# Flash_STM32.net
KiCad netlist of a schematic drawn in Altium Designer
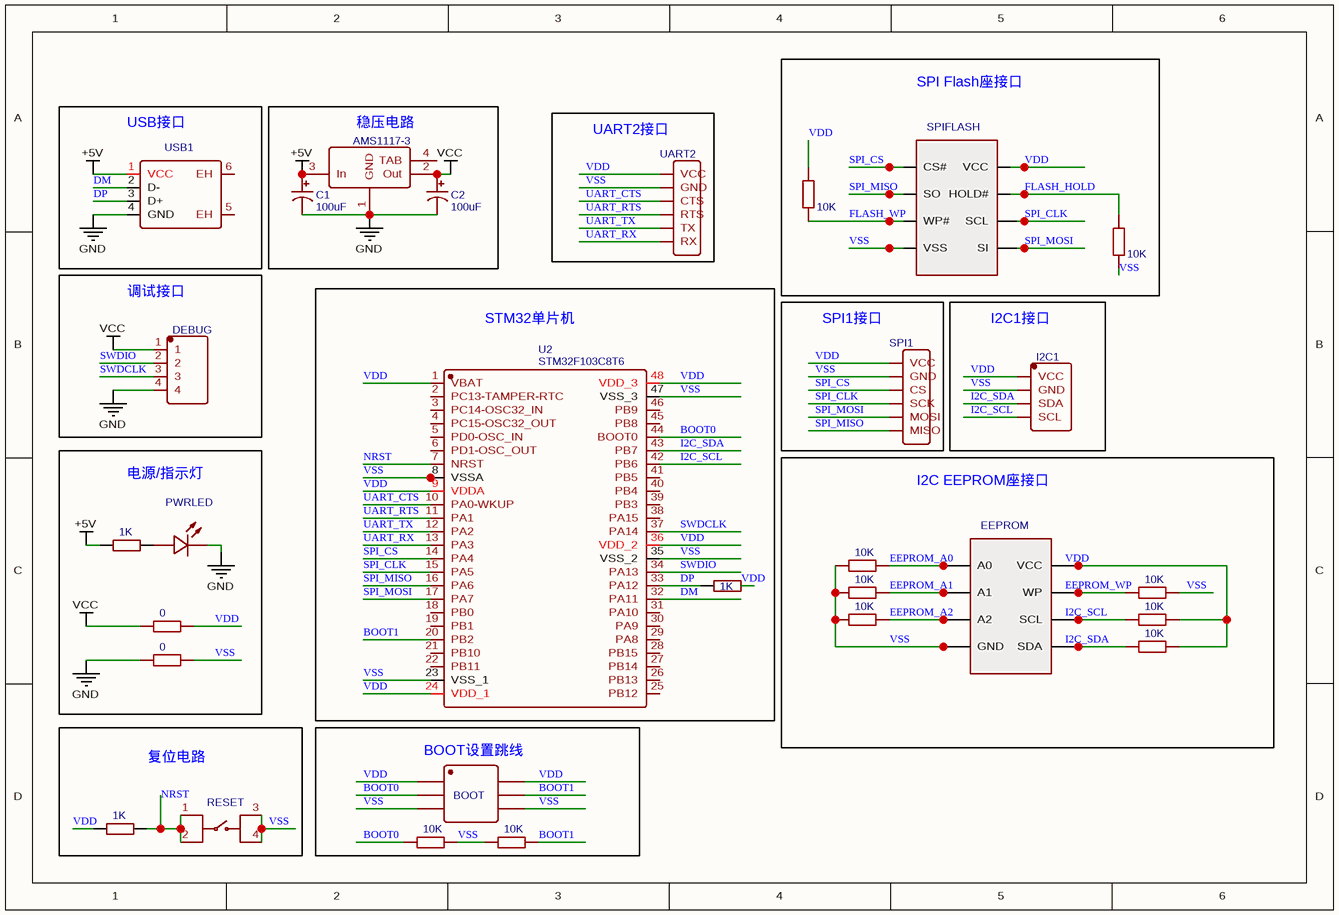
[diagram p0: Flash烧录器STM32版.schdoc]

(export (version "E")
  (design (tool "Eeschema 10.0.6"))
  (components
    (comp (ref "AMS1117-3")
      (value "AMS1117-3.3_C165482")
      (fields
        (field (name "BOM_SUPPLIER PART") "C165482")
        (field (name "BOM_MANUFACTURER PART") "AMS1117-3.3")
        (field (name "CONTRIBUTOR") "LCSC")
      )
      (libsource (lib "altium-import") (part "root_0_AMS1117-3.3_C165482_"))
    )
    (comp (ref "BOOT")
      (value "210S-2*3P L=11.6MMGold-plated black")
      (fields (field (name "BOM_SUPPLIER PART") "C124384") (field (name "CONTRIBUTOR") "LCSC"))
      (libsource (lib "altium-import") (part "root_0_210S-2*3P L=11.6MMGold-plated black_"))
    )
    (comp (ref "C1")
      (value "100uF")
      (fields
        (field (name "BOM_MANUFACTURER PART") "RVT1A101M0505")
        (field (name "BOM_SUPPLIER PART") "C3347")
      )
      (libsource (lib "altium-import") (part "root_0_100uF_"))
    )
    (comp (ref "C2")
      (value "100uF")
      (fields
        (field (name "BOM_MANUFACTURER PART") "RVT1A101M0505")
        (field (name "BOM_SUPPLIER PART") "C3347")
      )
      (libsource (lib "altium-import") (part "root_0_100uF_"))
    )
    (comp (ref "DEBUG")
      (value "MTP125-1104S1")
      (fields (field (name "BOM_SUPPLIER PART") "C358686") (field (name "CONTRIBUTOR") "LCSC"))
      (libsource (lib "altium-import") (part "root_0_MTP125-1104S1_"))
    )
    (comp (ref "EEPROM")
      (value "DS1009-08AT1NX-0A2")
      (fields (field (name "BOM_SUPPLIER PART") "C72124"))
      (libsource (lib "altium-import") (part "root_0_DS1009-08AT1NX-0A2_"))
    )
    (comp (ref "I2C1")
      (value "MTP125-1104S1")
      (fields (field (name "BOM_SUPPLIER PART") "C358686") (field (name "CONTRIBUTOR") "LCSC"))
      (libsource (lib "") (part "root_0_MTP125-1104S1__1"))
    )
    (comp (ref "PWRLED")
      (value "MHL3014SRTS")
      (fields (field (name "BOM_SUPPLIER PART") "C397053") (field (name "CONTRIBUTOR") "LCSC"))
      (libsource (lib "altium-import") (part "root_0_MHL3014SRTS_"))
    )
    (comp (ref "R1")
      (value "1K")
      (fields
        (field (name "BOM_MANUFACTURER PART") "0603WAF1001T5E")
        (field (name "BOM_SUPPLIER PART") "C21190")
      )
      (libsource (lib "altium-import") (part "root_0_1K_"))
    )
    (comp (ref "R2")
      (value "1K")
      (fields
        (field (name "BOM_MANUFACTURER PART") "0603WAF1001T5E")
        (field (name "BOM_SUPPLIER PART") "C21190")
      )
      (libsource (lib "altium-import") (part "root_0_1K_"))
    )
    (comp (ref "R3")
      (value "10K")
      (fields
        (field (name "BOM_SUPPLIER PART") "C237800")
        (field (name "BOM_MANUFACTURER PART") "RMCF1206JT10K0")
        (field (name "CONTRIBUTOR") "LCSC")
      )
      (libsource (lib "altium-import") (part "root_0_10K_"))
    )
    (comp (ref "R4")
      (value "10K")
      (fields
        (field (name "BOM_SUPPLIER PART") "C237800")
        (field (name "BOM_MANUFACTURER PART") "RMCF1206JT10K0")
        (field (name "CONTRIBUTOR") "LCSC")
      )
      (libsource (lib "altium-import") (part "root_0_10K_"))
    )
    (comp (ref "R5")
      (value "10K")
      (fields
        (field (name "BOM_SUPPLIER PART") "C237800")
        (field (name "BOM_MANUFACTURER PART") "RMCF1206JT10K0")
        (field (name "CONTRIBUTOR") "LCSC")
      )
      (libsource (lib "altium-import") (part "root_1_10K_"))
    )
    (comp (ref "R6")
      (value "10K")
      (fields
        (field (name "BOM_SUPPLIER PART") "C237800")
        (field (name "BOM_MANUFACTURER PART") "RMCF1206JT10K0")
        (field (name "CONTRIBUTOR") "LCSC")
      )
      (libsource (lib "altium-import") (part "root_1_10K_"))
    )
    (comp (ref "R7")
      (value "10K")
      (fields
        (field (name "BOM_SUPPLIER PART") "C237800")
        (field (name "BOM_MANUFACTURER PART") "RMCF1206JT10K0")
        (field (name "CONTRIBUTOR") "LCSC")
      )
      (libsource (lib "altium-import") (part "root_2_10K_"))
    )
    (comp (ref "R8")
      (value "10K")
      (fields
        (field (name "BOM_SUPPLIER PART") "C237800")
        (field (name "BOM_MANUFACTURER PART") "RMCF1206JT10K0")
        (field (name "CONTRIBUTOR") "LCSC")
      )
      (libsource (lib "altium-import") (part "root_2_10K_"))
    )
    (comp (ref "R9")
      (value "10K")
      (fields
        (field (name "BOM_SUPPLIER PART") "C237800")
        (field (name "BOM_MANUFACTURER PART") "RMCF1206JT10K0")
        (field (name "CONTRIBUTOR") "LCSC")
      )
      (libsource (lib "altium-import") (part "root_2_10K_"))
    )
    (comp (ref "R10")
      (value "10K")
      (fields
        (field (name "BOM_SUPPLIER PART") "C237800")
        (field (name "BOM_MANUFACTURER PART") "RMCF1206JT10K0")
        (field (name "CONTRIBUTOR") "LCSC")
      )
      (libsource (lib "altium-import") (part "root_2_10K_"))
    )
    (comp (ref "R11")
      (value "10K")
      (fields
        (field (name "BOM_SUPPLIER PART") "C237800")
        (field (name "BOM_MANUFACTURER PART") "RMCF1206JT10K0")
        (field (name "CONTRIBUTOR") "LCSC")
      )
      (libsource (lib "altium-import") (part "root_2_10K_"))
    )
    (comp (ref "R12")
      (value "10K")
      (fields
        (field (name "BOM_SUPPLIER PART") "C237800")
        (field (name "BOM_MANUFACTURER PART") "RMCF1206JT10K0")
        (field (name "CONTRIBUTOR") "LCSC")
      )
      (libsource (lib "altium-import") (part "root_2_10K_"))
    )
    (comp (ref "R13")
      (value "0")
      (fields
        (field (name "BOM_SUPPLIER PART") "C254574")
        (field (name "BOM_MANUFACTURER PART") "RM10FTN0")
        (field (name "CONTRIBUTOR") "LCSC")
      )
      (libsource (lib "altium-import") (part "root_0_0_"))
    )
    (comp (ref "R14")
      (value "0")
      (fields
        (field (name "BOM_SUPPLIER PART") "C254574")
        (field (name "BOM_MANUFACTURER PART") "RM10FTN0")
        (field (name "CONTRIBUTOR") "LCSC")
      )
      (libsource (lib "altium-import") (part "root_0_0_"))
    )
    (comp (ref "R15")
      (value "1K")
      (fields
        (field (name "BOM_MANUFACTURER PART") "0603WAF1001T5E")
        (field (name "BOM_SUPPLIER PART") "C21190")
      )
      (libsource (lib "altium-import") (part "root_0_1K_"))
    )
    (comp (ref "RESET")
      (value "K2-6639SP-C4SC-04")
      (fields (field (name "BOM_SUPPLIER PART") "C83206"))
      (libsource (lib "altium-import") (part "root_0_K2-6639SP-C4SC-04_"))
    )
    (comp (ref "SPI1")
      (value "Header-Male-2.54_1x6")
      (fields (field (name "BOM_SUPPLIER PART") "C37208"))
      (libsource (lib "altium-import") (part "root_0_Header-Male-2.54_1x6_"))
    )
    (comp (ref "SPIFLASH")
      (value "DS1009-08AT1NX-0A2")
      (fields (field (name "BOM_SUPPLIER PART") "C72124"))
      (libsource (lib "altium-import") (part "root_0_DS1009-08AT1NX-0A2_"))
    )
    (comp (ref "U2")
      (value "STM32F103C8T6")
      (fields (field (name "BOM_SUPPLIER PART") "C8734"))
      (libsource (lib "altium-import") (part "root_0_STM32F103C8T6_"))
    )
    (comp (ref "UART2")
      (value "Header-Male-2.54_1x6")
      (fields (field (name "BOM_SUPPLIER PART") "C37208"))
      (libsource (lib "altium-import") (part "root_0_Header-Male-2.54_1x6_"))
    )
    (comp (ref "USB1")
      (value "USB-05")
      (fields (field (name "BOM_SUPPLIER PART") "C112454") (field (name "CONTRIBUTOR") "LCSC"))
      (libsource (lib "altium-import") (part "root_0_USB-05_"))
    )
  )
  (nets
    (net (code "1") (name "+5V") (class "Default")
      (node (ref "AMS1117-3") (pin "3") (pinfunction "In_3") (pintype "passive"))
      (node (ref "C1") (pin "1") (pinfunction "1_1") (pintype "passive"))
      (node (ref "R1") (pin "1") (pinfunction "1_1") (pintype "passive"))
      (node (ref "USB1") (pin "1") (pinfunction "VCC_1") (pintype "passive"))
    )
    (net (code "2") (name "/BOOT0") (class "Default")
      (node (ref "BOOT") (pin "3") (pinfunction "3_3") (pintype "passive"))
      (node (ref "R3") (pin "1") (pinfunction "1_1") (pintype "passive"))
      (node (ref "U2") (pin "44") (pinfunction "BOOT0_44") (pintype "passive"))
    )
    (net (code "3") (name "/BOOT1") (class "Default")
      (node (ref "BOOT") (pin "4") (pinfunction "4_4") (pintype "passive"))
      (node (ref "R4") (pin "2") (pinfunction "2_2") (pintype "passive"))
      (node (ref "U2") (pin "20") (pinfunction "PB2_20") (pintype "passive"))
    )
    (net (code "4") (name "/DM") (class "Default")
      (node (ref "U2") (pin "32") (pinfunction "PA11_32") (pintype "passive"))
      (node (ref "USB1") (pin "2") (pinfunction "D-_2") (pintype "passive"))
    )
    (net (code "5") (name "/DP") (class "Default")
      (node (ref "R15") (pin "1") (pinfunction "1_1") (pintype "passive"))
      (node (ref "U2") (pin "33") (pinfunction "PA12_33") (pintype "passive"))
      (node (ref "USB1") (pin "3") (pinfunction "D+_3") (pintype "passive"))
    )
    (net (code "6") (name "/EEPROM_A0") (class "Default")
      (node (ref "EEPROM") (pin "1") (pinfunction "CS#_1") (pintype "passive"))
      (node (ref "R8") (pin "1") (pinfunction "1_1") (pintype "passive"))
    )
    (net (code "7") (name "/EEPROM_A1") (class "Default")
      (node (ref "EEPROM") (pin "2") (pinfunction "SO_2") (pintype "passive"))
      (node (ref "R11") (pin "1") (pinfunction "1_1") (pintype "passive"))
    )
    (net (code "8") (name "/EEPROM_A2") (class "Default")
      (node (ref "EEPROM") (pin "3") (pinfunction "WP#_3") (pintype "passive"))
      (node (ref "R12") (pin "1") (pinfunction "1_1") (pintype "passive"))
    )
    (net (code "9") (name "/EEPROM_WP") (class "Default")
      (node (ref "EEPROM") (pin "7") (pinfunction "HOLD#_7") (pintype "passive"))
      (node (ref "R10") (pin "2") (pinfunction "2_2") (pintype "passive"))
    )
    (net (code "10") (name "/FLASH_HOLD") (class "Default")
      (node (ref "R6") (pin "2") (pinfunction "2_2") (pintype "passive"))
      (node (ref "SPIFLASH") (pin "7") (pinfunction "HOLD#_7") (pintype "passive"))
    )
    (net (code "11") (name "/FLASH_WP") (class "Default")
      (node (ref "R5") (pin "1") (pinfunction "1_1") (pintype "passive"))
      (node (ref "SPIFLASH") (pin "3") (pinfunction "WP#_3") (pintype "passive"))
    )
    (net (code "12") (name "/I2C_SCL") (class "Default")
      (node (ref "EEPROM") (pin "6") (pinfunction "SCL_6") (pintype "passive"))
      (node (ref "I2C1") (pin "4") (pinfunction "SCL_4") (pintype "passive"))
      (node (ref "R9") (pin "2") (pinfunction "2_2") (pintype "passive"))
      (node (ref "U2") (pin "42") (pinfunction "PB6_42") (pintype "passive"))
    )
    (net (code "13") (name "/I2C_SDA") (class "Default")
      (node (ref "EEPROM") (pin "5") (pinfunction "SI_5") (pintype "passive"))
      (node (ref "I2C1") (pin "3") (pinfunction "SDA_3") (pintype "passive"))
      (node (ref "R7") (pin "2") (pinfunction "2_2") (pintype "passive"))
      (node (ref "U2") (pin "43") (pinfunction "PB7_43") (pintype "passive"))
    )
    (net (code "14") (name "/NRST") (class "Default")
      (node (ref "R2") (pin "2") (pinfunction "2_2") (pintype "passive"))
      (node (ref "RESET") (pin "1") (pinfunction "1_1") (pintype "passive"))
      (node (ref "RESET") (pin "2") (pinfunction "2_2") (pintype "passive"))
      (node (ref "U2") (pin "7") (pinfunction "NRST_7") (pintype "passive"))
    )
    (net (code "15") (name "/SPI_CLK") (class "Default")
      (node (ref "SPI1") (pin "4") (pinfunction "RTS_4") (pintype "passive"))
      (node (ref "SPIFLASH") (pin "6") (pinfunction "SCL_6") (pintype "passive"))
      (node (ref "U2") (pin "15") (pinfunction "PA5_15") (pintype "passive"))
    )
    (net (code "16") (name "/SPI_CS") (class "Default")
      (node (ref "SPI1") (pin "3") (pinfunction "CTS_3") (pintype "passive"))
      (node (ref "SPIFLASH") (pin "1") (pinfunction "CS#_1") (pintype "passive"))
      (node (ref "U2") (pin "14") (pinfunction "PA4_14") (pintype "passive"))
    )
    (net (code "17") (name "/SPI_MISO") (class "Default")
      (node (ref "SPI1") (pin "6") (pinfunction "RX_6") (pintype "passive"))
      (node (ref "SPIFLASH") (pin "2") (pinfunction "SO_2") (pintype "passive"))
      (node (ref "U2") (pin "16") (pinfunction "PA6_16") (pintype "passive"))
    )
    (net (code "18") (name "/SPI_MOSI") (class "Default")
      (node (ref "SPI1") (pin "5") (pinfunction "TX_5") (pintype "passive"))
      (node (ref "SPIFLASH") (pin "5") (pinfunction "SI_5") (pintype "passive"))
      (node (ref "U2") (pin "17") (pinfunction "PA7_17") (pintype "passive"))
    )
    (net (code "19") (name "/SWDCLK") (class "Default")
      (node (ref "DEBUG") (pin "3") (pinfunction "3_3") (pintype "passive"))
      (node (ref "U2") (pin "37") (pinfunction "PA14_37") (pintype "passive"))
    )
    (net (code "20") (name "/SWDIO") (class "Default")
      (node (ref "DEBUG") (pin "2") (pinfunction "2_2") (pintype "passive"))
      (node (ref "U2") (pin "34") (pinfunction "PA13_34") (pintype "passive"))
    )
    (net (code "21") (name "/UART_CTS") (class "Default")
      (node (ref "U2") (pin "10") (pinfunction "PA0-WKUP_10") (pintype "passive"))
      (node (ref "UART2") (pin "3") (pinfunction "CTS_3") (pintype "passive"))
    )
    (net (code "22") (name "/UART_RTS") (class "Default")
      (node (ref "U2") (pin "11") (pinfunction "PA1_11") (pintype "passive"))
      (node (ref "UART2") (pin "4") (pinfunction "RTS_4") (pintype "passive"))
    )
    (net (code "23") (name "/UART_RX") (class "Default")
      (node (ref "U2") (pin "13") (pinfunction "PA3_13") (pintype "passive"))
      (node (ref "UART2") (pin "6") (pinfunction "RX_6") (pintype "passive"))
    )
    (net (code "24") (name "/UART_TX") (class "Default")
      (node (ref "U2") (pin "12") (pinfunction "PA2_12") (pintype "passive"))
      (node (ref "UART2") (pin "5") (pinfunction "TX_5") (pintype "passive"))
    )
    (net (code "25") (name "/VDD") (class "Default")
      (node (ref "BOOT") (pin "1") (pinfunction "1_1") (pintype "passive"))
      (node (ref "BOOT") (pin "2") (pinfunction "2_2") (pintype "passive"))
      (node (ref "EEPROM") (pin "8") (pinfunction "VCC_8") (pintype "passive"))
      (node (ref "I2C1") (pin "1") (pinfunction "VCC_1") (pintype "passive"))
      (node (ref "R13") (pin "2") (pinfunction "2_2") (pintype "passive"))
      (node (ref "R15") (pin "2") (pinfunction "2_2") (pintype "passive"))
      (node (ref "R2") (pin "1") (pinfunction "1_1") (pintype "passive"))
      (node (ref "R5") (pin "2") (pinfunction "2_2") (pintype "passive"))
      (node (ref "R7") (pin "1") (pinfunction "1_1") (pintype "passive"))
      (node (ref "R9") (pin "1") (pinfunction "1_1") (pintype "passive"))
      (node (ref "SPI1") (pin "1") (pinfunction "VCC_1") (pintype "passive"))
      (node (ref "SPIFLASH") (pin "8") (pinfunction "VCC_8") (pintype "passive"))
      (node (ref "U2") (pin "1") (pinfunction "VBAT_1") (pintype "passive"))
      (node (ref "U2") (pin "24") (pinfunction "VDD_1_24") (pintype "passive"))
      (node (ref "U2") (pin "36") (pinfunction "VDD_2_36") (pintype "passive"))
      (node (ref "U2") (pin "48") (pinfunction "VDD_3_48") (pintype "passive"))
      (node (ref "U2") (pin "9") (pinfunction "VDDA_9") (pintype "passive"))
      (node (ref "UART2") (pin "1") (pinfunction "VCC_1") (pintype "passive"))
    )
    (net (code "26") (name "/VSS") (class "Default")
      (node (ref "BOOT") (pin "5") (pinfunction "5_5") (pintype "passive"))
      (node (ref "BOOT") (pin "6") (pinfunction "6_6") (pintype "passive"))
      (node (ref "EEPROM") (pin "4") (pinfunction "VSS_4") (pintype "passive"))
      (node (ref "I2C1") (pin "2") (pinfunction "GND_2") (pintype "passive"))
      (node (ref "R10") (pin "1") (pinfunction "1_1") (pintype "passive"))
      (node (ref "R11") (pin "2") (pinfunction "2_2") (pintype "passive"))
      (node (ref "R12") (pin "2") (pinfunction "2_2") (pintype "passive"))
      (node (ref "R14") (pin "2") (pinfunction "2_2") (pintype "passive"))
      (node (ref "R3") (pin "2") (pinfunction "2_2") (pintype "passive"))
      (node (ref "R4") (pin "1") (pinfunction "1_1") (pintype "passive"))
      (node (ref "R6") (pin "1") (pinfunction "1_1") (pintype "passive"))
      (node (ref "R8") (pin "2") (pinfunction "2_2") (pintype "passive"))
      (node (ref "RESET") (pin "3") (pinfunction "3_3") (pintype "passive"))
      (node (ref "RESET") (pin "4") (pinfunction "4_4") (pintype "passive"))
      (node (ref "SPI1") (pin "2") (pinfunction "GND_2") (pintype "passive"))
      (node (ref "SPIFLASH") (pin "4") (pinfunction "VSS_4") (pintype "passive"))
      (node (ref "U2") (pin "23") (pinfunction "VSS_1_23") (pintype "passive"))
      (node (ref "U2") (pin "35") (pinfunction "VSS_2_35") (pintype "passive"))
      (node (ref "U2") (pin "47") (pinfunction "VSS_3_47") (pintype "passive"))
      (node (ref "U2") (pin "8") (pinfunction "VSSA_8") (pintype "passive"))
      (node (ref "UART2") (pin "2") (pinfunction "GND_2") (pintype "passive"))
    )
    (net (code "27") (name "GND") (class "Default")
      (node (ref "AMS1117-3") (pin "1") (pinfunction "GND_1") (pintype "passive"))
      (node (ref "C1") (pin "2") (pinfunction "2_2") (pintype "passive"))
      (node (ref "C2") (pin "2") (pinfunction "2_2") (pintype "passive"))
      (node (ref "DEBUG") (pin "4") (pinfunction "4_4") (pintype "passive"))
      (node (ref "PWRLED") (pin "2") (pinfunction "K_2") (pintype "passive"))
      (node (ref "R14") (pin "1") (pinfunction "1_1") (pintype "passive"))
      (node (ref "USB1") (pin "4") (pinfunction "GND_4") (pintype "passive"))
    )
    (net (code "28") (name "Net-(PWRLED-A)") (class "Default")
      (node (ref "PWRLED") (pin "1") (pinfunction "A_1") (pintype "passive"))
      (node (ref "R1") (pin "2") (pinfunction "2_2") (pintype "passive"))
    )
    (net (code "29") (name "VCC") (class "Default")
      (node (ref "AMS1117-3") (pin "2") (pinfunction "Out_2") (pintype "passive"))
      (node (ref "C2") (pin "1") (pinfunction "1_1") (pintype "passive"))
      (node (ref "DEBUG") (pin "1") (pinfunction "1_1") (pintype "passive"))
      (node (ref "R13") (pin "1") (pinfunction "1_1") (pintype "passive"))
    )
    (net (code "30") (name "unconnected-(AMS1117-3-TAB-Pad4)") (class "Default")
      (node (ref "AMS1117-3") (pin "4") (pinfunction "TAB_4") (pintype "passive"))
    )
    (net (code "31") (name "unconnected-(U2-PA8-Pad29)") (class "Default")
      (node (ref "U2") (pin "29") (pinfunction "PA8_29") (pintype "passive"))
    )
    (net (code "32") (name "unconnected-(U2-PA9-Pad30)") (class "Default")
      (node (ref "U2") (pin "30") (pinfunction "PA9_30") (pintype "passive"))
    )
    (net (code "33") (name "unconnected-(U2-PA10-Pad31)") (class "Default")
      (node (ref "U2") (pin "31") (pinfunction "PA10_31") (pintype "passive"))
    )
    (net (code "34") (name "unconnected-(U2-PA15-Pad38)") (class "Default")
      (node (ref "U2") (pin "38") (pinfunction "PA15_38") (pintype "passive"))
    )
    (net (code "35") (name "unconnected-(U2-PB0-Pad18)") (class "Default")
      (node (ref "U2") (pin "18") (pinfunction "PB0_18") (pintype "passive"))
    )
    (net (code "36") (name "unconnected-(U2-PB1-Pad19)") (class "Default")
      (node (ref "U2") (pin "19") (pinfunction "PB1_19") (pintype "passive"))
    )
    (net (code "37") (name "unconnected-(U2-PB3-Pad39)") (class "Default")
      (node (ref "U2") (pin "39") (pinfunction "PB3_39") (pintype "passive"))
    )
    (net (code "38") (name "unconnected-(U2-PB4-Pad40)") (class "Default")
      (node (ref "U2") (pin "40") (pinfunction "PB4_40") (pintype "passive"))
    )
    (net (code "39") (name "unconnected-(U2-PB5-Pad41)") (class "Default")
      (node (ref "U2") (pin "41") (pinfunction "PB5_41") (pintype "passive"))
    )
    (net (code "40") (name "unconnected-(U2-PB8-Pad45)") (class "Default")
      (node (ref "U2") (pin "45") (pinfunction "PB8_45") (pintype "passive"))
    )
    (net (code "41") (name "unconnected-(U2-PB9-Pad46)") (class "Default")
      (node (ref "U2") (pin "46") (pinfunction "PB9_46") (pintype "passive"))
    )
    (net (code "42") (name "unconnected-(U2-PB10-Pad21)") (class "Default")
      (node (ref "U2") (pin "21") (pinfunction "PB10_21") (pintype "passive"))
    )
    (net (code "43") (name "unconnected-(U2-PB11-Pad22)") (class "Default")
      (node (ref "U2") (pin "22") (pinfunction "PB11_22") (pintype "passive"))
    )
    (net (code "44") (name "unconnected-(U2-PB12-Pad25)") (class "Default")
      (node (ref "U2") (pin "25") (pinfunction "PB12_25") (pintype "passive"))
    )
    (net (code "45") (name "unconnected-(U2-PB13-Pad26)") (class "Default")
      (node (ref "U2") (pin "26") (pinfunction "PB13_26") (pintype "passive"))
    )
    (net (code "46") (name "unconnected-(U2-PB14-Pad27)") (class "Default")
      (node (ref "U2") (pin "27") (pinfunction "PB14_27") (pintype "passive"))
    )
    (net (code "47") (name "unconnected-(U2-PB15-Pad28)") (class "Default")
      (node (ref "U2") (pin "28") (pinfunction "PB15_28") (pintype "passive"))
    )
    (net (code "48") (name "unconnected-(U2-PC13-TAMPER-RTC-Pad2)") (class "Default")
      (node (ref "U2") (pin "2") (pinfunction "PC13-TAMPER-RTC_2") (pintype "passive"))
    )
    (net (code "49") (name "unconnected-(U2-PC14-OSC32_IN-Pad3)") (class "Default")
      (node (ref "U2") (pin "3") (pinfunction "PC14-OSC32_IN_3") (pintype "passive"))
    )
    (net (code "50") (name "unconnected-(U2-PC15-OSC32_OUT-Pad4)") (class "Default")
      (node (ref "U2") (pin "4") (pinfunction "PC15-OSC32_OUT_4") (pintype "passive"))
    )
    (net (code "51") (name "unconnected-(U2-PD0-OSC_IN-Pad5)") (class "Default")
      (node (ref "U2") (pin "5") (pinfunction "PD0-OSC_IN_5") (pintype "passive"))
    )
    (net (code "52") (name "unconnected-(U2-PD1-OSC_OUT-Pad6)") (class "Default")
      (node (ref "U2") (pin "6") (pinfunction "PD1-OSC_OUT_6") (pintype "passive"))
    )
    (net (code "53") (name "unconnected-(USB1-EH-Pad5)") (class "Default")
      (node (ref "USB1") (pin "5") (pinfunction "EH_5") (pintype "passive"))
    )
    (net (code "54") (name "unconnected-(USB1-EH-Pad6)") (class "Default")
      (node (ref "USB1") (pin "6") (pinfunction "EH_6") (pintype "passive"))
    )
  )
)
